# level_shifter_adj_15V.net
KiCad netlist of a schematic drawn in EAGLE
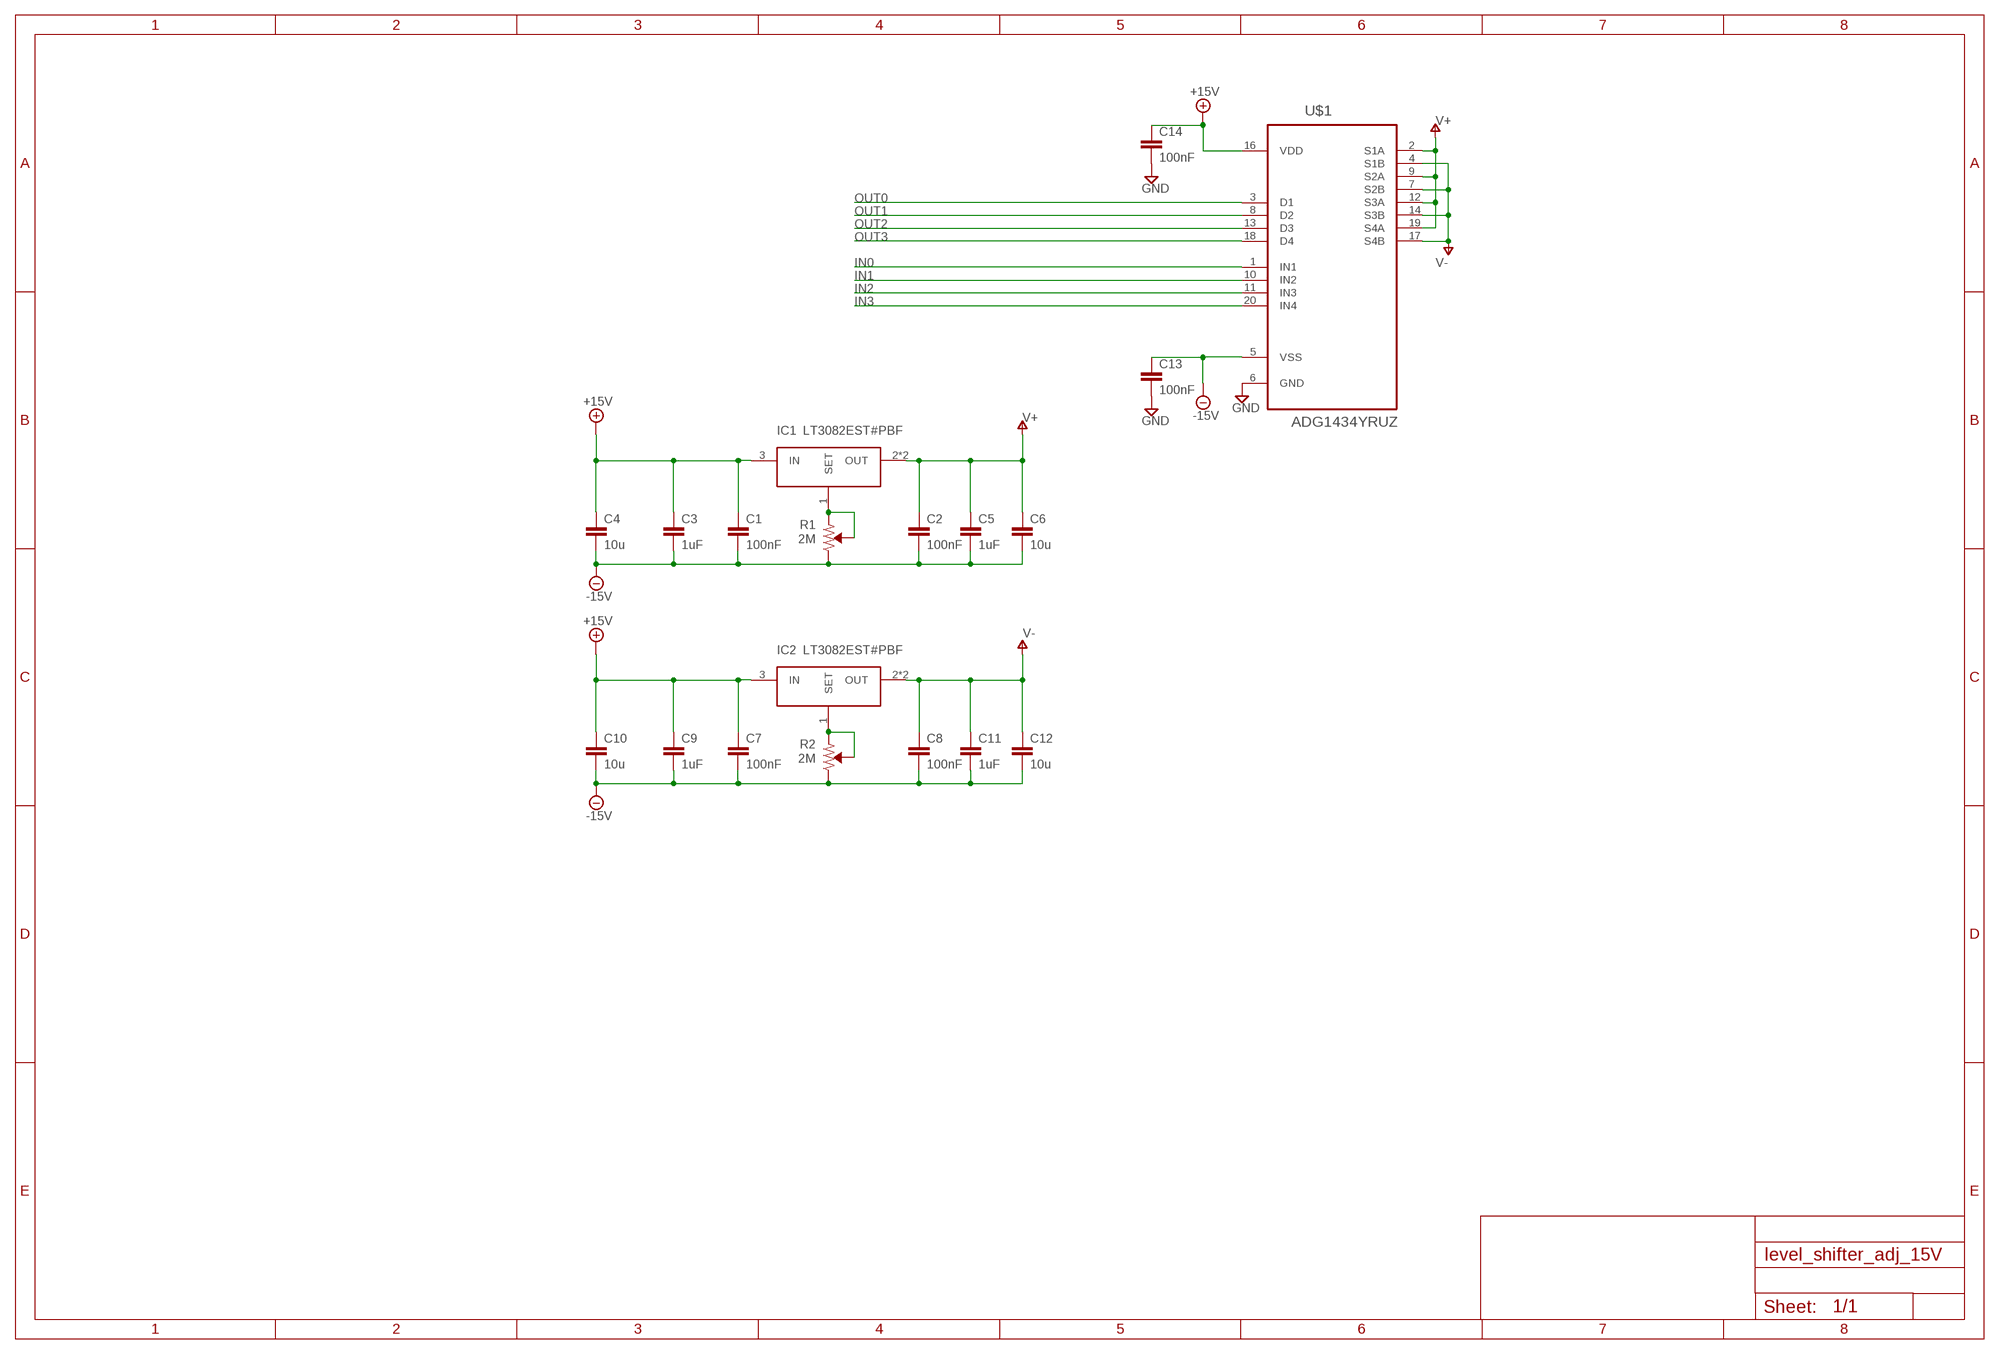
[diagram p0: schematic, sheet 1]

(export (version "E")
  (design (tool "Eeschema 10.0.6"))
  (components
    (comp (ref "C1")
      (value "100nF")
      (footprint "eagle-import:C0402")
      (libsource (lib "eagle-import") (part "C-EUC0402"))
    )
    (comp (ref "C2")
      (value "100nF")
      (footprint "eagle-import:C0402")
      (libsource (lib "eagle-import") (part "C-EUC0402"))
    )
    (comp (ref "C3")
      (value "1uF")
      (footprint "eagle-import:C0402")
      (libsource (lib "eagle-import") (part "C-EUC0402"))
    )
    (comp (ref "C4")
      (value "10u")
      (footprint "eagle-import:C0603")
      (libsource (lib "eagle-import") (part "C-EUC0603"))
    )
    (comp (ref "C5")
      (value "1uF")
      (footprint "eagle-import:C0402")
      (libsource (lib "eagle-import") (part "C-EUC0402"))
    )
    (comp (ref "C6")
      (value "10u")
      (footprint "eagle-import:C0603")
      (libsource (lib "eagle-import") (part "C-EUC0603"))
    )
    (comp (ref "C7")
      (value "100nF")
      (footprint "eagle-import:C0402")
      (libsource (lib "eagle-import") (part "C-EUC0402"))
    )
    (comp (ref "C8")
      (value "100nF")
      (footprint "eagle-import:C0402")
      (libsource (lib "eagle-import") (part "C-EUC0402"))
    )
    (comp (ref "C9")
      (value "1uF")
      (footprint "eagle-import:C0402")
      (libsource (lib "eagle-import") (part "C-EUC0402"))
    )
    (comp (ref "C10")
      (value "10u")
      (footprint "eagle-import:C0603")
      (libsource (lib "eagle-import") (part "C-EUC0603"))
    )
    (comp (ref "C11")
      (value "1uF")
      (footprint "eagle-import:C0402")
      (libsource (lib "eagle-import") (part "C-EUC0402"))
    )
    (comp (ref "C12")
      (value "10u")
      (footprint "eagle-import:C0603")
      (libsource (lib "eagle-import") (part "C-EUC0603"))
    )
    (comp (ref "C13")
      (value "100nF")
      (footprint "eagle-import:C0402")
      (libsource (lib "eagle-import") (part "C-EUC0402"))
    )
    (comp (ref "C14")
      (value "100nF")
      (footprint "eagle-import:C0402")
      (libsource (lib "eagle-import") (part "C-EUC0402"))
    )
    (comp (ref "IC1")
      (value "LT3082EST#PBF")
      (footprint "eagle-import:SOT230P700X180-4N")
      (fields (field (name "MOUSER_PART_NUMBER") "584-LT3082EST#PBF"))
      (libsource (lib "eagle-import") (part "LT3082EST#PBF"))
    )
    (comp (ref "IC2")
      (value "LT3082EST#PBF")
      (footprint "eagle-import:SOT230P700X180-4N")
      (fields (field (name "MOUSER_PART_NUMBER") "584-LT3082EST#PBF"))
      (libsource (lib "eagle-import") (part "LT3082EST#PBF"))
    )
    (comp (ref "R1")
      (value "2M")
      (footprint "eagle-import:TRIM_3296Y-1-202LF")
      (libsource (lib "eagle-import") (part "3296Y-1"))
    )
    (comp (ref "R2")
      (value "2M")
      (footprint "eagle-import:TRIM_3296Y-1-202LF")
      (libsource (lib "eagle-import") (part "3296Y-1"))
    )
    (comp (ref "U$1")
      (value "ADG1434YRUZ")
      (footprint "eagle-import:SOP65P640X120-20N")
      (libsource (lib "eagle-import") (part "ADG1434YRUZ"))
    )
  )
  (nets
    (net (code "1") (name "+15V") (class "Default")
      (node (ref "C1") (pin "1") (pinfunction "1_1") (pintype "passive"))
      (node (ref "C10") (pin "1") (pinfunction "1_1") (pintype "passive"))
      (node (ref "C14") (pin "1") (pinfunction "1_1") (pintype "passive"))
      (node (ref "C3") (pin "1") (pinfunction "1_1") (pintype "passive"))
      (node (ref "C4") (pin "1") (pinfunction "1_1") (pintype "passive"))
      (node (ref "C7") (pin "1") (pinfunction "1_1") (pintype "passive"))
      (node (ref "C9") (pin "1") (pinfunction "1_1") (pintype "passive"))
      (node (ref "IC1") (pin "3") (pinfunction "IN_3") (pintype "bidirectional"))
      (node (ref "IC2") (pin "3") (pinfunction "IN_3") (pintype "bidirectional"))
      (node (ref "U$1") (pin "16") (pinfunction "VDD_16") (pintype "power_in"))
    )
    (net (code "2") (name "-15V") (class "Default")
      (node (ref "C1") (pin "2") (pinfunction "2_2") (pintype "passive"))
      (node (ref "C10") (pin "2") (pinfunction "2_2") (pintype "passive"))
      (node (ref "C11") (pin "2") (pinfunction "2_2") (pintype "passive"))
      (node (ref "C12") (pin "2") (pinfunction "2_2") (pintype "passive"))
      (node (ref "C13") (pin "1") (pinfunction "1_1") (pintype "passive"))
      (node (ref "C2") (pin "2") (pinfunction "2_2") (pintype "passive"))
      (node (ref "C3") (pin "2") (pinfunction "2_2") (pintype "passive"))
      (node (ref "C4") (pin "2") (pinfunction "2_2") (pintype "passive"))
      (node (ref "C5") (pin "2") (pinfunction "2_2") (pintype "passive"))
      (node (ref "C6") (pin "2") (pinfunction "2_2") (pintype "passive"))
      (node (ref "C7") (pin "2") (pinfunction "2_2") (pintype "passive"))
      (node (ref "C8") (pin "2") (pinfunction "2_2") (pintype "passive"))
      (node (ref "C9") (pin "2") (pinfunction "2_2") (pintype "passive"))
      (node (ref "R1") (pin "3") (pinfunction "CW_3") (pintype "passive"))
      (node (ref "R2") (pin "3") (pinfunction "CW_3") (pintype "passive"))
      (node (ref "U$1") (pin "5") (pinfunction "VSS_5") (pintype "power_in"))
    )
    (net (code "3") (name "/IN0") (class "Default")
      (node (ref "U$1") (pin "1") (pinfunction "IN1_1") (pintype "input"))
    )
    (net (code "4") (name "/IN1") (class "Default")
      (node (ref "U$1") (pin "10") (pinfunction "IN2_10") (pintype "input"))
    )
    (net (code "5") (name "/IN2") (class "Default")
      (node (ref "U$1") (pin "11") (pinfunction "IN3_11") (pintype "input"))
    )
    (net (code "6") (name "/IN3") (class "Default")
      (node (ref "U$1") (pin "20") (pinfunction "IN4_20") (pintype "input"))
    )
    (net (code "7") (name "/OUT0") (class "Default")
      (node (ref "U$1") (pin "3") (pinfunction "D1_3") (pintype "bidirectional"))
    )
    (net (code "8") (name "/OUT1") (class "Default")
      (node (ref "U$1") (pin "8") (pinfunction "D2_8") (pintype "bidirectional"))
    )
    (net (code "9") (name "/OUT2") (class "Default")
      (node (ref "U$1") (pin "13") (pinfunction "D3_13") (pintype "bidirectional"))
    )
    (net (code "10") (name "/OUT3") (class "Default")
      (node (ref "U$1") (pin "18") (pinfunction "D4_18") (pintype "bidirectional"))
    )
    (net (code "11") (name "GND") (class "Default")
      (node (ref "C13") (pin "2") (pinfunction "2_2") (pintype "passive"))
      (node (ref "C14") (pin "2") (pinfunction "2_2") (pintype "passive"))
      (node (ref "U$1") (pin "6") (pinfunction "GND_6") (pintype "passive"))
    )
    (net (code "12") (name "Net-(IC1-SET)") (class "Default")
      (node (ref "IC1") (pin "1") (pinfunction "SET_1") (pintype "bidirectional"))
      (node (ref "R1") (pin "1") (pinfunction "CCW_1") (pintype "passive"))
      (node (ref "R1") (pin "2") (pinfunction "WIPER_2") (pintype "passive"))
    )
    (net (code "13") (name "Net-(IC2-SET)") (class "Default")
      (node (ref "IC2") (pin "1") (pinfunction "SET_1") (pintype "bidirectional"))
      (node (ref "R2") (pin "1") (pinfunction "CCW_1") (pintype "passive"))
      (node (ref "R2") (pin "2") (pinfunction "WIPER_2") (pintype "passive"))
    )
    (net (code "14") (name "V+") (class "Default")
      (node (ref "C2") (pin "1") (pinfunction "1_1") (pintype "passive"))
      (node (ref "C5") (pin "1") (pinfunction "1_1") (pintype "passive"))
      (node (ref "C6") (pin "1") (pinfunction "1_1") (pintype "passive"))
      (node (ref "IC1") (pin "2") (pinfunction "OUT_2") (pintype "bidirectional"))
      (node (ref "IC1") (pin "4") (pinfunction "OUT_4") (pintype "bidirectional"))
      (node (ref "U$1") (pin "12") (pinfunction "S3A_12") (pintype "bidirectional"))
      (node (ref "U$1") (pin "19") (pinfunction "S4A_19") (pintype "bidirectional"))
      (node (ref "U$1") (pin "2") (pinfunction "S1A_2") (pintype "bidirectional"))
      (node (ref "U$1") (pin "9") (pinfunction "S2A_9") (pintype "bidirectional"))
    )
    (net (code "15") (name "V-") (class "Default")
      (node (ref "C11") (pin "1") (pinfunction "1_1") (pintype "passive"))
      (node (ref "C12") (pin "1") (pinfunction "1_1") (pintype "passive"))
      (node (ref "C8") (pin "1") (pinfunction "1_1") (pintype "passive"))
      (node (ref "IC2") (pin "2") (pinfunction "OUT_2") (pintype "bidirectional"))
      (node (ref "IC2") (pin "4") (pinfunction "OUT_4") (pintype "bidirectional"))
      (node (ref "U$1") (pin "14") (pinfunction "S3B_14") (pintype "bidirectional"))
      (node (ref "U$1") (pin "17") (pinfunction "S4B_17") (pintype "bidirectional"))
      (node (ref "U$1") (pin "4") (pinfunction "S1B_4") (pintype "bidirectional"))
      (node (ref "U$1") (pin "7") (pinfunction "S2B_7") (pintype "bidirectional"))
    )
  )
)
